# habexfemto.net
KiCad netlist of a schematic drawn in EAGLE
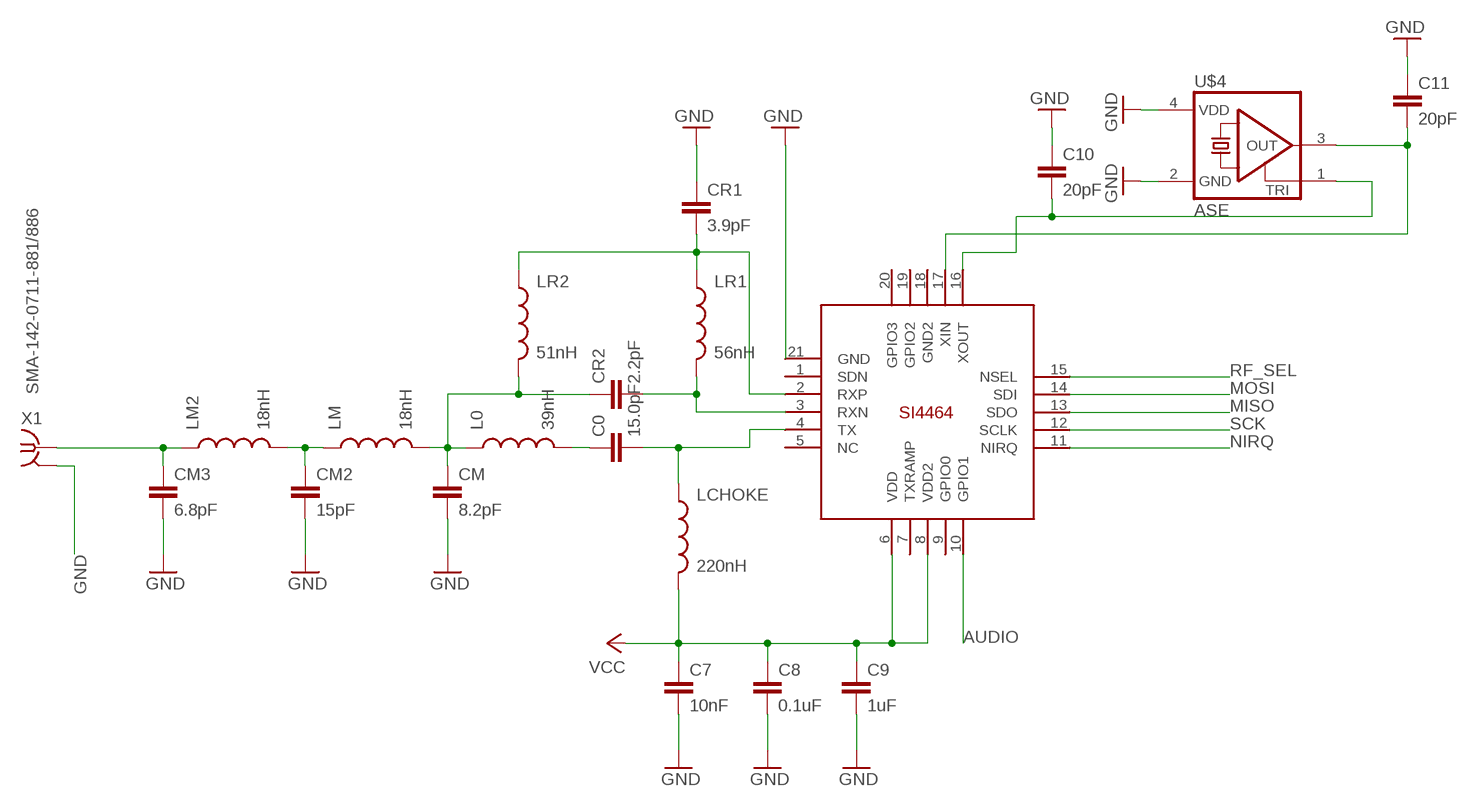
[diagram p0: schematic, sheet 1]
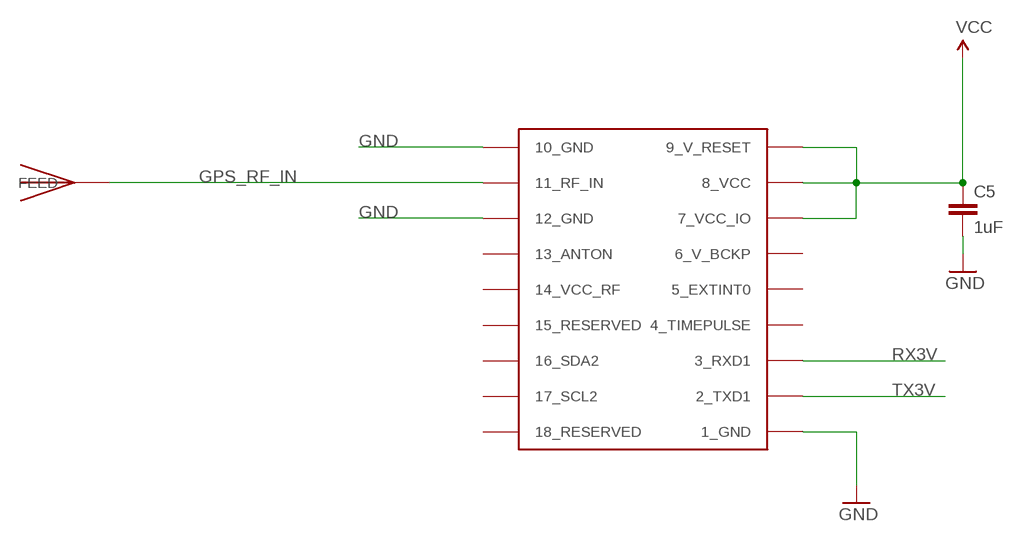
[diagram p1: schematic, sheet 2]
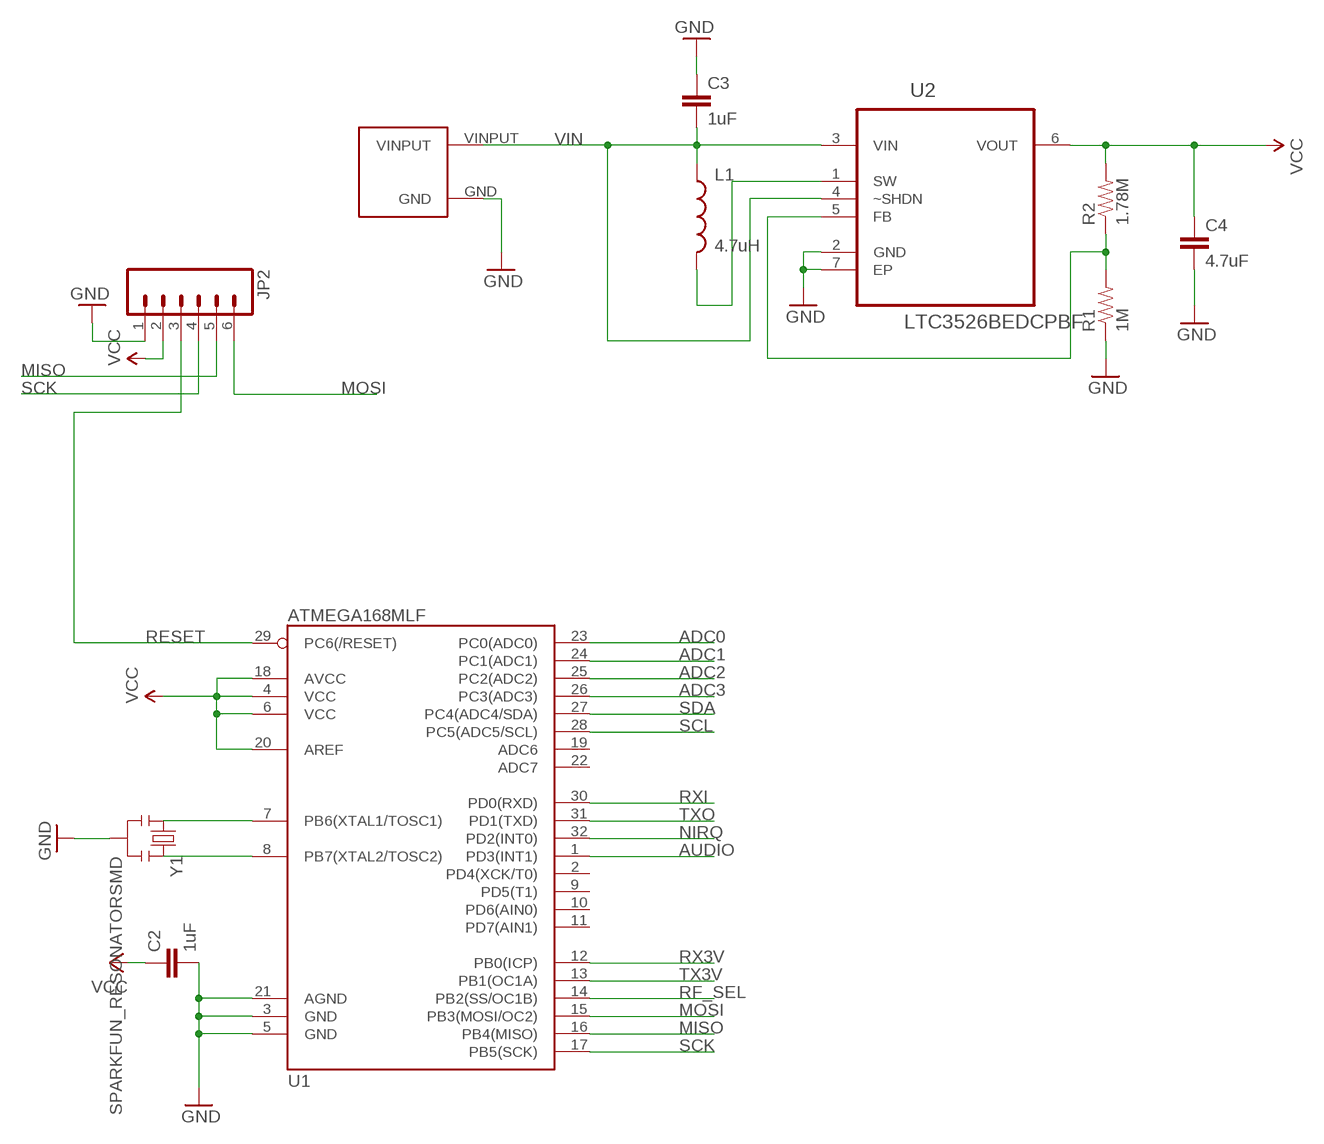
[diagram p2: schematic, sheet 3]

(export (version "E")
  (design (tool "Eeschema 10.0.6"))
  (components
    (comp (ref "C5")
      (value "1uF")
      (footprint "eagle-import:0402-CAP")
      (libsource (lib "eagle-import") (part "CAP0402-CAP"))
    )
    (comp (ref "U$2")
      (value "UBLOX_MAX-6")
      (footprint "eagle-import:UBLOX_MAX-6")
      (libsource (lib "eagle-import") (part "UBLOX_MAX-6"))
    )
    (comp (ref "U$3")
      (value "JTI_ANTENNA-1575AT43A40")
      (footprint "eagle-import:JTI_ANTENNA-1575AT43A40")
      (libsource (lib "eagle-import") (part "JTI_ANTENNA-1575AT43A40"))
    )
    (comp (ref "C2")
      (value "1uF")
      (footprint "eagle-import:0402-CAP")
      (libsource (lib "eagle-import") (part "CAP0402-CAP"))
    )
    (comp (ref "C3")
      (value "1uF")
      (footprint "eagle-import:0402-CAP")
      (libsource (lib "eagle-import") (part "CAP0402-CAP"))
    )
    (comp (ref "C4")
      (value "4.7uF")
      (footprint "eagle-import:0402-CAP")
      (libsource (lib "eagle-import") (part "CAP0402-CAP"))
    )
    (comp (ref "JP2")
      (value "M06EM406")
      (footprint "eagle-import:EM406")
      (libsource (lib "eagle-import") (part "M06EM406"))
    )
    (comp (ref "L1")
      (value "4.7uH")
      (footprint "eagle-import:0603")
      (libsource (lib "eagle-import") (part "INDUCTOR0603"))
    )
    (comp (ref "R1")
      (value "1M")
      (footprint "eagle-import:0402-RES")
      (libsource (lib "eagle-import") (part "RESISTOR0402-RES"))
    )
    (comp (ref "R2")
      (value "1.78M")
      (footprint "eagle-import:0402-RES")
      (libsource (lib "eagle-import") (part "RESISTOR0402-RES"))
    )
    (comp (ref "U$5")
      (value "POWERPADS")
      (footprint "eagle-import:POWERPADS")
      (libsource (lib "eagle-import") (part "POWERPADS"))
    )
    (comp (ref "U1")
      (value "ATMEGA168MLF")
      (footprint "eagle-import:MLF32")
      (libsource (lib "eagle-import") (part "ATMEGA168MLF"))
    )
    (comp (ref "U2")
      (value "LTC3526BEDCPBF")
      (footprint "eagle-import:DFN200X200X80-7N")
      (fields (field (name "MPN") "LTC3526BEDC#PBF"))
      (libsource (lib "eagle-import") (part "LTC3526BEDCPBF"))
    )
    (comp (ref "Y1")
      (value "SPARKFUN_RESONATORSMD")
      (footprint "eagle-import:SPARKFUN_RESONATOR-SMD")
      (libsource (lib "eagle-import") (part "SPARKFUN_RESONATORSMD"))
    )
    (comp (ref "C0")
      (value "15.0pF")
      (footprint "eagle-import:0402-CAP")
      (libsource (lib "eagle-import") (part "CAP0402-CAP"))
    )
    (comp (ref "C7")
      (value "10nF")
      (footprint "eagle-import:0402-CAP")
      (libsource (lib "eagle-import") (part "CAP0402-CAP"))
    )
    (comp (ref "C8")
      (value "0.1uF")
      (footprint "eagle-import:0402-CAP")
      (libsource (lib "eagle-import") (part "CAP0402-CAP"))
    )
    (comp (ref "C9")
      (value "1uF")
      (footprint "eagle-import:0402-CAP")
      (libsource (lib "eagle-import") (part "CAP0402-CAP"))
    )
    (comp (ref "C10")
      (value "20pF")
      (footprint "eagle-import:0402-CAP")
      (libsource (lib "eagle-import") (part "CAP0402-CAP"))
    )
    (comp (ref "C11")
      (value "20pF")
      (footprint "eagle-import:0402-CAP")
      (libsource (lib "eagle-import") (part "CAP0402-CAP"))
    )
    (comp (ref "CM")
      (value "8.2pF")
      (footprint "eagle-import:0402-CAP")
      (libsource (lib "eagle-import") (part "CAP0402-CAP"))
    )
    (comp (ref "CM2")
      (value "15pF")
      (footprint "eagle-import:0402-CAP")
      (libsource (lib "eagle-import") (part "CAP0402-CAP"))
    )
    (comp (ref "CM3")
      (value "6.8pF")
      (footprint "eagle-import:0402-CAP")
      (libsource (lib "eagle-import") (part "CAP0402-CAP"))
    )
    (comp (ref "CR1")
      (value "3.9pF")
      (footprint "eagle-import:0402-CAP")
      (libsource (lib "eagle-import") (part "CAP0402-CAP"))
    )
    (comp (ref "CR2")
      (value "2.2pF")
      (footprint "eagle-import:0402-CAP")
      (libsource (lib "eagle-import") (part "CAP0402-CAP"))
    )
    (comp (ref "L0")
      (value "39nH")
      (footprint "eagle-import:C0402")
      (libsource (lib "eagle-import") (part "INDUCTOR0402"))
    )
    (comp (ref "LCHOKE")
      (value "220nH")
      (footprint "eagle-import:C0402")
      (libsource (lib "eagle-import") (part "INDUCTOR0402"))
    )
    (comp (ref "LM")
      (value "18nH")
      (footprint "eagle-import:C0402")
      (libsource (lib "eagle-import") (part "INDUCTOR0402"))
    )
    (comp (ref "LM2")
      (value "18nH")
      (footprint "eagle-import:C0402")
      (libsource (lib "eagle-import") (part "INDUCTOR0402"))
    )
    (comp (ref "LR1")
      (value "56nH")
      (footprint "eagle-import:C0402")
      (libsource (lib "eagle-import") (part "INDUCTOR0402"))
    )
    (comp (ref "LR2")
      (value "51nH")
      (footprint "eagle-import:C0402")
      (libsource (lib "eagle-import") (part "INDUCTOR0402"))
    )
    (comp (ref "U$1")
      (value "SI4464")
      (footprint "eagle-import:QFN20+GNDPAD")
      (libsource (lib "eagle-import") (part "SI4464"))
    )
    (comp (ref "U$4")
      (value "ASE")
      (footprint "eagle-import:ASE")
      (libsource (lib "eagle-import") (part "ASE"))
    )
    (comp (ref "X1")
      (value "SMA-142-0711-881/886")
      (footprint "eagle-import:J502-ND-142-0711-881_886")
      (fields (field (name "MF") "JOHNSON COMPONENTS") (field (name "MPN") "142-0711-881"))
      (libsource (lib "eagle-import") (part "SMA-142-0711-881/886"))
    )
  )
  (nets
    (net (code "1") (name "ADC0") (class "Default")
      (node (ref "U1") (pin "23") (pinfunction "PC0(ADC0)_23") (pintype "bidirectional"))
    )
    (net (code "2") (name "ADC1") (class "Default")
      (node (ref "U1") (pin "24") (pinfunction "PC1(ADC1)_24") (pintype "bidirectional"))
    )
    (net (code "3") (name "ADC2") (class "Default")
      (node (ref "U1") (pin "25") (pinfunction "PC2(ADC2)_25") (pintype "bidirectional"))
    )
    (net (code "4") (name "ADC3") (class "Default")
      (node (ref "U1") (pin "26") (pinfunction "PC3(ADC3)_26") (pintype "bidirectional"))
    )
    (net (code "5") (name "AUDIO") (class "Default")
      (node (ref "U$1") (pin "10") (pinfunction "GPIO1_10") (pintype "bidirectional"))
      (node (ref "U1") (pin "1") (pinfunction "PD3(INT1)_1") (pintype "bidirectional"))
    )
    (net (code "6") (name "GND") (class "Default")
      (node (ref "C10") (pin "1") (pinfunction "1_1") (pintype "passive"))
      (node (ref "C11") (pin "1") (pinfunction "1_1") (pintype "passive"))
      (node (ref "C2") (pin "2") (pinfunction "2_2") (pintype "passive"))
      (node (ref "C3") (pin "1") (pinfunction "1_1") (pintype "passive"))
      (node (ref "C4") (pin "2") (pinfunction "2_2") (pintype "passive"))
      (node (ref "C5") (pin "2") (pinfunction "2_2") (pintype "passive"))
      (node (ref "C7") (pin "2") (pinfunction "2_2") (pintype "passive"))
      (node (ref "C8") (pin "2") (pinfunction "2_2") (pintype "passive"))
      (node (ref "C9") (pin "2") (pinfunction "2_2") (pintype "passive"))
      (node (ref "CM") (pin "2") (pinfunction "2_2") (pintype "passive"))
      (node (ref "CM2") (pin "2") (pinfunction "2_2") (pintype "passive"))
      (node (ref "CM3") (pin "2") (pinfunction "2_2") (pintype "passive"))
      (node (ref "CR1") (pin "1") (pinfunction "1_1") (pintype "passive"))
      (node (ref "JP2") (pin "1") (pinfunction "1_1") (pintype "passive"))
      (node (ref "R1") (pin "1") (pinfunction "1_1") (pintype "passive"))
      (node (ref "U$1") (pin "21") (pinfunction "GND_21") (pintype "bidirectional"))
      (node (ref "U$2") (pin "10_GND") (pinfunction "10_GND_10_GND") (pintype "power_in"))
      (node (ref "U$2") (pin "12_GND") (pinfunction "12_GND_12_GND") (pintype "power_in"))
      (node (ref "U$2") (pin "1_GND") (pinfunction "1_GND_1_GND") (pintype "power_in"))
      (node (ref "U$4") (pin "2") (pinfunction "GND_2") (pintype "power_in"))
      (node (ref "U$4") (pin "4") (pinfunction "VDD_4") (pintype "power_in"))
      (node (ref "U$5") (pin "GND") (pinfunction "GND_GND") (pintype "bidirectional"))
      (node (ref "U1") (pin "21") (pinfunction "AGND_21") (pintype "bidirectional"))
      (node (ref "U1") (pin "3") (pinfunction "GND_3") (pintype "bidirectional"))
      (node (ref "U1") (pin "5") (pinfunction "GND_5") (pintype "bidirectional"))
      (node (ref "U2") (pin "2") (pinfunction "GND_2") (pintype "passive"))
      (node (ref "U2") (pin "7") (pinfunction "EP_7") (pintype "passive"))
      (node (ref "X1") (pin "G@1") (pinfunction "2_G@1") (pintype "passive"))
      (node (ref "X1") (pin "G@2") (pinfunction "2_G@2") (pintype "passive"))
      (node (ref "X1") (pin "G@3") (pinfunction "2_G@3") (pintype "passive"))
      (node (ref "X1") (pin "G@4") (pinfunction "2_G@4") (pintype "passive"))
      (node (ref "Y1") (pin "2") (pinfunction "2_2") (pintype "passive"))
    )
    (net (code "7") (name "GPS_RF_IN") (class "Default")
      (node (ref "U$2") (pin "11_RF_IN") (pinfunction "11_RF_IN_11_RF_IN") (pintype "bidirectional"))
      (node (ref "U$3") (pin "FEED") (pinfunction "FEED_FEED") (pintype "bidirectional"))
    )
    (net (code "8") (name "MISO") (class "Default")
      (node (ref "JP2") (pin "5") (pinfunction "5_5") (pintype "passive"))
      (node (ref "U$1") (pin "13") (pinfunction "SDO_13") (pintype "bidirectional"))
      (node (ref "U1") (pin "16") (pinfunction "PB4(MISO)_16") (pintype "bidirectional"))
    )
    (net (code "9") (name "MOSI") (class "Default")
      (node (ref "JP2") (pin "6") (pinfunction "6_6") (pintype "passive"))
      (node (ref "U$1") (pin "14") (pinfunction "SDI_14") (pintype "bidirectional"))
      (node (ref "U1") (pin "15") (pinfunction "PB3(MOSI/OC2)_15") (pintype "bidirectional"))
    )
    (net (code "10") (name "NIRQ") (class "Default")
      (node (ref "U$1") (pin "11") (pinfunction "NIRQ_11") (pintype "bidirectional"))
      (node (ref "U1") (pin "32") (pinfunction "PD2(INT0)_32") (pintype "bidirectional"))
    )
    (net (code "11") (name "Net-(C0-Pad1)") (class "Default")
      (node (ref "C0") (pin "1") (pinfunction "1_1") (pintype "passive"))
      (node (ref "L0") (pin "2") (pinfunction "2_2") (pintype "passive"))
    )
    (net (code "12") (name "Net-(CM-Pad1)") (class "Default")
      (node (ref "CM") (pin "1") (pinfunction "1_1") (pintype "passive"))
      (node (ref "CR2") (pin "1") (pinfunction "1_1") (pintype "passive"))
      (node (ref "L0") (pin "1") (pinfunction "1_1") (pintype "passive"))
      (node (ref "LM") (pin "2") (pinfunction "2_2") (pintype "passive"))
      (node (ref "LR2") (pin "2") (pinfunction "2_2") (pintype "passive"))
    )
    (net (code "13") (name "Net-(CM2-Pad1)") (class "Default")
      (node (ref "CM2") (pin "1") (pinfunction "1_1") (pintype "passive"))
      (node (ref "LM") (pin "1") (pinfunction "1_1") (pintype "passive"))
      (node (ref "LM2") (pin "2") (pinfunction "2_2") (pintype "passive"))
    )
    (net (code "14") (name "Net-(CM3-Pad1)") (class "Default")
      (node (ref "CM3") (pin "1") (pinfunction "1_1") (pintype "passive"))
      (node (ref "LM2") (pin "1") (pinfunction "1_1") (pintype "passive"))
      (node (ref "X1") (pin "1") (pinfunction "1_1") (pintype "passive"))
    )
    (net (code "15") (name "Net-(U$1-RXN)") (class "Default")
      (node (ref "CR2") (pin "2") (pinfunction "2_2") (pintype "passive"))
      (node (ref "LR1") (pin "2") (pinfunction "2_2") (pintype "passive"))
      (node (ref "U$1") (pin "3") (pinfunction "RXN_3") (pintype "bidirectional"))
    )
    (net (code "16") (name "Net-(U$1-RXP)") (class "Default")
      (node (ref "CR1") (pin "2") (pinfunction "2_2") (pintype "passive"))
      (node (ref "LR1") (pin "1") (pinfunction "1_1") (pintype "passive"))
      (node (ref "LR2") (pin "1") (pinfunction "1_1") (pintype "passive"))
      (node (ref "U$1") (pin "2") (pinfunction "RXP_2") (pintype "bidirectional"))
    )
    (net (code "17") (name "Net-(U$1-TX)") (class "Default")
      (node (ref "C0") (pin "2") (pinfunction "2_2") (pintype "passive"))
      (node (ref "LCHOKE") (pin "1") (pinfunction "1_1") (pintype "passive"))
      (node (ref "U$1") (pin "4") (pinfunction "TX_4") (pintype "bidirectional"))
    )
    (net (code "18") (name "Net-(U$1-XIN)") (class "Default")
      (node (ref "C11") (pin "2") (pinfunction "2_2") (pintype "passive"))
      (node (ref "U$1") (pin "17") (pinfunction "XIN_17") (pintype "bidirectional"))
      (node (ref "U$4") (pin "3") (pinfunction "OUT_3") (pintype "output"))
    )
    (net (code "19") (name "Net-(U$1-XOUT)") (class "Default")
      (node (ref "C10") (pin "2") (pinfunction "2_2") (pintype "passive"))
      (node (ref "U$1") (pin "16") (pinfunction "XOUT_16") (pintype "bidirectional"))
      (node (ref "U$4") (pin "1") (pinfunction "TRI_1") (pintype "input"))
    )
    (net (code "20") (name "Net-(U1-PB6(XTAL1{slash}TOSC1))") (class "Default")
      (node (ref "U1") (pin "7") (pinfunction "PB6(XTAL1/TOSC1)_7") (pintype "bidirectional"))
      (node (ref "Y1") (pin "1") (pinfunction "1_1") (pintype "passive"))
    )
    (net (code "21") (name "Net-(U1-PB7(XTAL2{slash}TOSC2))") (class "Default")
      (node (ref "U1") (pin "8") (pinfunction "PB7(XTAL2/TOSC2)_8") (pintype "bidirectional"))
      (node (ref "Y1") (pin "3") (pinfunction "3_3") (pintype "passive"))
    )
    (net (code "22") (name "Net-(U2-FB)") (class "Default")
      (node (ref "R1") (pin "2") (pinfunction "2_2") (pintype "passive"))
      (node (ref "R2") (pin "1") (pinfunction "1_1") (pintype "passive"))
      (node (ref "U2") (pin "5") (pinfunction "FB_5") (pintype "input"))
    )
    (net (code "23") (name "Net-(U2-SW)") (class "Default")
      (node (ref "L1") (pin "2") (pinfunction "2_2") (pintype "passive"))
      (node (ref "U2") (pin "1") (pinfunction "SW_1") (pintype "passive"))
    )
    (net (code "24") (name "RESET") (class "Default")
      (node (ref "JP2") (pin "3") (pinfunction "3_3") (pintype "passive"))
      (node (ref "U1") (pin "29") (pinfunction "PC6(/RESET)_29") (pintype "bidirectional"))
    )
    (net (code "25") (name "RF_SEL") (class "Default")
      (node (ref "U$1") (pin "15") (pinfunction "NSEL_15") (pintype "bidirectional"))
      (node (ref "U1") (pin "14") (pinfunction "PB2(SS/OC1B)_14") (pintype "bidirectional"))
    )
    (net (code "26") (name "RX3V") (class "Default")
      (node (ref "U$2") (pin "3_RXD1") (pinfunction "3_RXD1_3_RXD1") (pintype "bidirectional"))
      (node (ref "U1") (pin "12") (pinfunction "PB0(ICP)_12") (pintype "bidirectional"))
    )
    (net (code "27") (name "RXI") (class "Default")
      (node (ref "U1") (pin "30") (pinfunction "PD0(RXD)_30") (pintype "bidirectional"))
    )
    (net (code "28") (name "SCK") (class "Default")
      (node (ref "JP2") (pin "4") (pinfunction "4_4") (pintype "passive"))
      (node (ref "U$1") (pin "12") (pinfunction "SCLK_12") (pintype "bidirectional"))
      (node (ref "U1") (pin "17") (pinfunction "PB5(SCK)_17") (pintype "bidirectional"))
    )
    (net (code "29") (name "SCL") (class "Default")
      (node (ref "U1") (pin "28") (pinfunction "PC5(ADC5/SCL)_28") (pintype "bidirectional"))
    )
    (net (code "30") (name "SDA") (class "Default")
      (node (ref "U1") (pin "27") (pinfunction "PC4(ADC4/SDA)_27") (pintype "bidirectional"))
    )
    (net (code "31") (name "TX3V") (class "Default")
      (node (ref "U$2") (pin "2_TXD1") (pinfunction "2_TXD1_2_TXD1") (pintype "bidirectional"))
      (node (ref "U1") (pin "13") (pinfunction "PB1(OC1A)_13") (pintype "bidirectional"))
    )
    (net (code "32") (name "TXO") (class "Default")
      (node (ref "U1") (pin "31") (pinfunction "PD1(TXD)_31") (pintype "bidirectional"))
    )
    (net (code "33") (name "VCC") (class "Default")
      (node (ref "C2") (pin "1") (pinfunction "1_1") (pintype "passive"))
      (node (ref "C4") (pin "1") (pinfunction "1_1") (pintype "passive"))
      (node (ref "C5") (pin "1") (pinfunction "1_1") (pintype "passive"))
      (node (ref "C7") (pin "1") (pinfunction "1_1") (pintype "passive"))
      (node (ref "C8") (pin "1") (pinfunction "1_1") (pintype "passive"))
      (node (ref "C9") (pin "1") (pinfunction "1_1") (pintype "passive"))
      (node (ref "JP2") (pin "2") (pinfunction "2_2") (pintype "passive"))
      (node (ref "LCHOKE") (pin "2") (pinfunction "2_2") (pintype "passive"))
      (node (ref "R2") (pin "2") (pinfunction "2_2") (pintype "passive"))
      (node (ref "U$1") (pin "6") (pinfunction "VDD_6") (pintype "bidirectional"))
      (node (ref "U$1") (pin "8") (pinfunction "VDD2_8") (pintype "bidirectional"))
      (node (ref "U$2") (pin "7_VCC_IO") (pinfunction "7_VCC_IO_7_VCC_IO") (pintype "power_in"))
      (node (ref "U$2") (pin "8_VCC") (pinfunction "8_VCC_8_VCC") (pintype "power_in"))
      (node (ref "U$2") (pin "9_V_RESET") (pinfunction "9_V_RESET_9_V_RESET") (pintype "power_in"))
      (node (ref "U1") (pin "18") (pinfunction "AVCC_18") (pintype "bidirectional"))
      (node (ref "U1") (pin "20") (pinfunction "AREF_20") (pintype "bidirectional"))
      (node (ref "U1") (pin "4") (pinfunction "VCC_4") (pintype "bidirectional"))
      (node (ref "U1") (pin "6") (pinfunction "VCC_6") (pintype "bidirectional"))
      (node (ref "U2") (pin "6") (pinfunction "VOUT_6") (pintype "output"))
    )
    (net (code "34") (name "VIN") (class "Default")
      (node (ref "C3") (pin "2") (pinfunction "2_2") (pintype "passive"))
      (node (ref "L1") (pin "1") (pinfunction "1_1") (pintype "passive"))
      (node (ref "U$5") (pin "VINPUT") (pinfunction "VINPUT_VINPUT") (pintype "bidirectional"))
      (node (ref "U2") (pin "3") (pinfunction "VIN_3") (pintype "power_in"))
      (node (ref "U2") (pin "4") (pinfunction "~{SHDN}_4") (pintype "input"))
    )
    (net (code "35") (name "unconnected-(U$1-GND2-Pad18)") (class "Default")
      (node (ref "U$1") (pin "18") (pinfunction "GND2_18") (pintype "bidirectional"))
    )
    (net (code "36") (name "unconnected-(U$1-GPIO0-Pad9)") (class "Default")
      (node (ref "U$1") (pin "9") (pinfunction "GPIO0_9") (pintype "bidirectional"))
    )
    (net (code "37") (name "unconnected-(U$1-GPIO2-Pad19)") (class "Default")
      (node (ref "U$1") (pin "19") (pinfunction "GPIO2_19") (pintype "bidirectional"))
    )
    (net (code "38") (name "unconnected-(U$1-GPIO3-Pad20)") (class "Default")
      (node (ref "U$1") (pin "20") (pinfunction "GPIO3_20") (pintype "bidirectional"))
    )
    (net (code "39") (name "unconnected-(U$1-NC -Pad5)") (class "Default")
      (node (ref "U$1") (pin "5") (pinfunction "NC _5") (pintype "bidirectional"))
    )
    (net (code "40") (name "unconnected-(U$1-SDN-Pad1)") (class "Default")
      (node (ref "U$1") (pin "1") (pinfunction "SDN_1") (pintype "bidirectional"))
    )
    (net (code "41") (name "unconnected-(U$1-TXRAMP-Pad7)") (class "Default")
      (node (ref "U$1") (pin "7") (pinfunction "TXRAMP_7") (pintype "bidirectional"))
    )
    (net (code "42") (name "unconnected-(U$2-Pad4_TIMEPULSE)") (class "Default")
      (node (ref "U$2") (pin "4_TIMEPULSE") (pinfunction "4_TIMEPULSE_4_TIMEPULSE") (pintype "bidirectional"))
    )
    (net (code "43") (name "unconnected-(U$2-Pad5_EXTINT0)") (class "Default")
      (node (ref "U$2") (pin "5_EXTINT0") (pinfunction "5_EXTINT0_5_EXTINT0") (pintype "bidirectional"))
    )
    (net (code "44") (name "unconnected-(U$2-Pad6_V_BCKP)") (class "Default")
      (node (ref "U$2") (pin "6_V_BCKP") (pinfunction "6_V_BCKP_6_V_BCKP") (pintype "bidirectional"))
    )
    (net (code "45") (name "unconnected-(U$2-Pad13_ANTON)") (class "Default")
      (node (ref "U$2") (pin "13_ANTON") (pinfunction "13_ANTON_13_ANTON") (pintype "bidirectional"))
    )
    (net (code "46") (name "unconnected-(U$2-Pad14_VCC_RF)") (class "Default")
      (node (ref "U$2") (pin "14_VCC_RF") (pinfunction "14_VCC_RF_14_VCC_RF") (pintype "bidirectional"))
    )
    (net (code "47") (name "unconnected-(U$2-Pad15_RESERVED)") (class "Default")
      (node (ref "U$2") (pin "15_RESERVED") (pinfunction "15_RESERVED_15_RESERVED") (pintype "bidirectional"))
    )
    (net (code "48") (name "unconnected-(U$2-Pad16_SDA2)") (class "Default")
      (node (ref "U$2") (pin "16_SDA2") (pinfunction "16_SDA2_16_SDA2") (pintype "bidirectional"))
    )
    (net (code "49") (name "unconnected-(U$2-Pad17_SCL2)") (class "Default")
      (node (ref "U$2") (pin "17_SCL2") (pinfunction "17_SCL2_17_SCL2") (pintype "bidirectional"))
    )
    (net (code "50") (name "unconnected-(U$2-Pad18_RESERVED)") (class "Default")
      (node (ref "U$2") (pin "18_RESERVED") (pinfunction "18_RESERVED_18_RESERVED") (pintype "bidirectional"))
    )
    (net (code "51") (name "unconnected-(U1-ADC6-Pad19)") (class "Default")
      (node (ref "U1") (pin "19") (pinfunction "ADC6_19") (pintype "bidirectional"))
    )
    (net (code "52") (name "unconnected-(U1-ADC7-Pad22)") (class "Default")
      (node (ref "U1") (pin "22") (pinfunction "ADC7_22") (pintype "bidirectional"))
    )
    (net (code "53") (name "unconnected-(U1-PD4(XCK{slash}T0)-Pad2)") (class "Default")
      (node (ref "U1") (pin "2") (pinfunction "PD4(XCK/T0)_2") (pintype "bidirectional"))
    )
    (net (code "54") (name "unconnected-(U1-PD5(T1)-Pad9)") (class "Default")
      (node (ref "U1") (pin "9") (pinfunction "PD5(T1)_9") (pintype "bidirectional"))
    )
    (net (code "55") (name "unconnected-(U1-PD6(AIN0)-Pad10)") (class "Default")
      (node (ref "U1") (pin "10") (pinfunction "PD6(AIN0)_10") (pintype "bidirectional"))
    )
    (net (code "56") (name "unconnected-(U1-PD7(AIN1)-Pad11)") (class "Default")
      (node (ref "U1") (pin "11") (pinfunction "PD7(AIN1)_11") (pintype "bidirectional"))
    )
  )
)
